# SN74AHC1G09_Breakout_Board.net
KiCad netlist of a schematic drawn in EAGLE
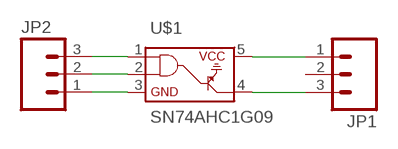
[diagram p0: schematic, sheet 1]

(export (version "E")
  (design (tool "Eeschema 10.0.6"))
  (components
    (comp (ref "JP1")
      (value "M03")
      (footprint "eagle-import:1X03")
      (libsource (lib "eagle-import") (part "M03"))
    )
    (comp (ref "JP2")
      (value "M03")
      (footprint "eagle-import:1X03")
      (libsource (lib "eagle-import") (part "M03"))
    )
    (comp (ref "U$1")
      (value "SN74AHC1G09")
      (footprint "eagle-import:SOT-23-5")
      (libsource (lib "eagle-import") (part "SN74AHC1G09"))
    )
  )
  (nets
    (net (code "1") (name "Net-(JP1-Pad1)") (class "Default")
      (node (ref "JP1") (pin "1") (pinfunction "1_1") (pintype "passive"))
      (node (ref "U$1") (pin "5") (pinfunction "5_5") (pintype "passive"))
    )
    (net (code "2") (name "Net-(JP1-Pad3)") (class "Default")
      (node (ref "JP1") (pin "3") (pinfunction "3_3") (pintype "passive"))
      (node (ref "U$1") (pin "4") (pinfunction "4_4") (pintype "passive"))
    )
    (net (code "3") (name "Net-(JP2-Pad1)") (class "Default")
      (node (ref "JP2") (pin "1") (pinfunction "1_1") (pintype "passive"))
      (node (ref "U$1") (pin "3") (pinfunction "3_3") (pintype "passive"))
    )
    (net (code "4") (name "Net-(JP2-Pad2)") (class "Default")
      (node (ref "JP2") (pin "2") (pinfunction "2_2") (pintype "passive"))
      (node (ref "U$1") (pin "2") (pinfunction "2_2") (pintype "passive"))
    )
    (net (code "5") (name "Net-(JP2-Pad3)") (class "Default")
      (node (ref "JP2") (pin "3") (pinfunction "3_3") (pintype "passive"))
      (node (ref "U$1") (pin "1") (pinfunction "1_1") (pintype "passive"))
    )
    (net (code "6") (name "unconnected-(JP1-Pad2)") (class "Default")
      (node (ref "JP1") (pin "2") (pinfunction "2_2") (pintype "passive"))
    )
  )
)
